# mcp801_test.net
KiCad netlist of a schematic drawn in EAGLE
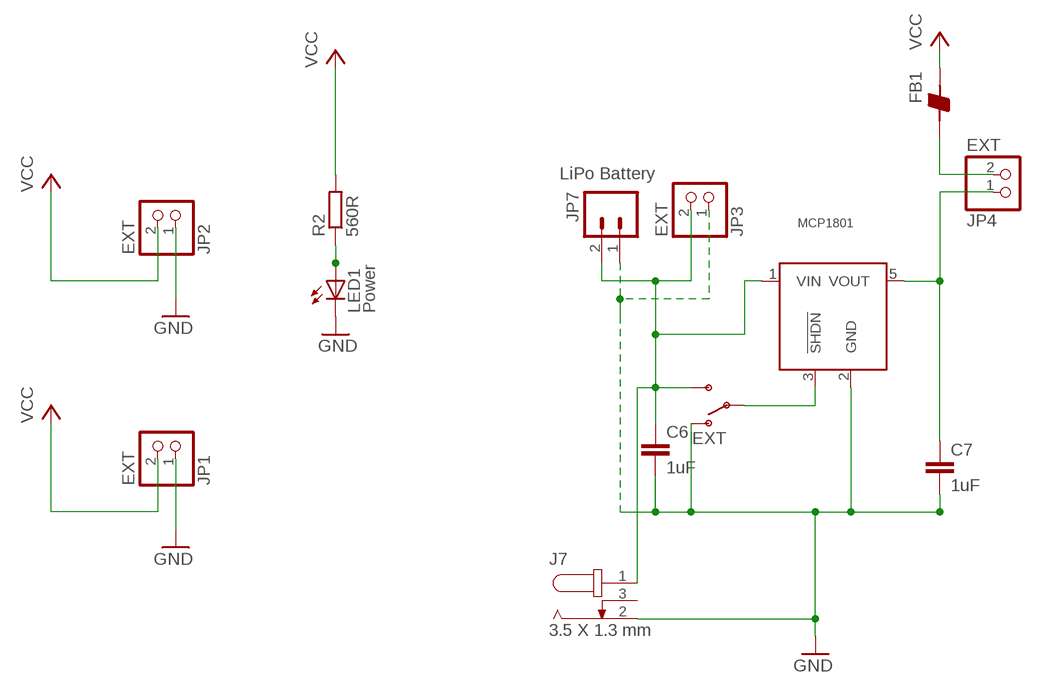
[diagram p0: schematic, sheet 1]

(export (version "E")
  (design (tool "Eeschema 10.0.6"))
  (components
    (comp (ref "C6")
      (value "1uF")
      (footprint "eagle-import:C0805")
      (libsource (lib "eagle-import") (part "C-EUC0805"))
    )
    (comp (ref "C7")
      (value "1uF")
      (footprint "eagle-import:C0805")
      (libsource (lib "eagle-import") (part "C-EUC0805"))
    )
    (comp (ref "FB1")
      (value "BEAD-0805")
      (footprint "eagle-import:0805")
      (libsource (lib "eagle-import") (part "BEAD-0805"))
    )
    (comp (ref "J7")
      (value "3.5 X 1.3 mm")
      (footprint "eagle-import:3.5X1.3MM_DC_JACK")
      (libsource (lib "eagle-import") (part "DC_JACK_3.5X1.3MM"))
    )
    (comp (ref "JP1")
      (value "EXT")
      (footprint "eagle-import:1X02")
      (libsource (lib "eagle-import") (part "PINHD-1X2"))
    )
    (comp (ref "JP2")
      (value "EXT")
      (footprint "eagle-import:1X02")
      (libsource (lib "eagle-import") (part "PINHD-1X2"))
    )
    (comp (ref "JP3")
      (value "EXT")
      (footprint "eagle-import:1X02")
      (libsource (lib "eagle-import") (part "PINHD-1X2"))
    )
    (comp (ref "JP4")
      (value "EXT")
      (footprint "eagle-import:1X02")
      (libsource (lib "eagle-import") (part "PINHD-1X2"))
    )
    (comp (ref "JP7")
      (value "LiPo Battery")
      (footprint "eagle-import:JST-2-PTH")
      (libsource (lib "eagle-import") (part "M02JST-PTH-2"))
    )
    (comp (ref "LED1")
      (value "Power")
      (footprint "eagle-import:CHIPLED_1206")
      (libsource (lib "eagle-import") (part "LEDCHIPLED_1206"))
    )
    (comp (ref "MCP1801")
      (value "MCP180XSOT-23-5")
      (footprint "eagle-import:SOT-23-5")
      (libsource (lib "eagle-import") (part "MCP180XSOT-23-5"))
    )
    (comp (ref "ON")
      (value "EXT")
      (footprint "eagle-import:SWITCH-SPDT")
      (libsource (lib "eagle-import") (part "SWITCH-SPSTPTH"))
    )
    (comp (ref "R2")
      (value "560R")
      (footprint "eagle-import:R0805")
      (libsource (lib "eagle-import") (part "R-EU_R0805"))
    )
  )
  (nets
    (net (code "1") (name "GND") (class "Default")
      (node (ref "C6") (pin "2") (pinfunction "2_2") (pintype "passive"))
      (node (ref "C7") (pin "2") (pinfunction "2_2") (pintype "passive"))
      (node (ref "J7") (pin "2") (pinfunction "2_2") (pintype "passive"))
      (node (ref "JP1") (pin "1") (pinfunction "1_1") (pintype "passive"))
      (node (ref "JP2") (pin "1") (pinfunction "1_1") (pintype "passive"))
      (node (ref "JP3") (pin "1") (pinfunction "1_1") (pintype "passive"))
      (node (ref "JP7") (pin "1") (pinfunction "1_1") (pintype "passive"))
      (node (ref "LED1") (pin "C") (pinfunction "C_C") (pintype "passive"))
      (node (ref "MCP1801") (pin "2") (pinfunction "GND_2") (pintype "power_in"))
      (node (ref "ON") (pin "1") (pinfunction "O_1") (pintype "passive"))
    )
    (net (code "2") (name "Net-(FB1-P$1)") (class "Default")
      (node (ref "FB1") (pin "1") (pinfunction "P$1_1") (pintype "passive"))
      (node (ref "JP4") (pin "2") (pinfunction "2_2") (pintype "passive"))
    )
    (net (code "3") (name "Net-(LED1-PadA)") (class "Default")
      (node (ref "LED1") (pin "A") (pinfunction "A_A") (pintype "passive"))
      (node (ref "R2") (pin "1") (pinfunction "1_1") (pintype "passive"))
    )
    (net (code "4") (name "Net-(MCP1801-VIN)") (class "Default")
      (node (ref "C6") (pin "1") (pinfunction "1_1") (pintype "passive"))
      (node (ref "J7") (pin "1") (pinfunction "1_1") (pintype "passive"))
      (node (ref "JP3") (pin "2") (pinfunction "2_2") (pintype "passive"))
      (node (ref "JP7") (pin "2") (pinfunction "2_2") (pintype "passive"))
      (node (ref "MCP1801") (pin "1") (pinfunction "VIN_1") (pintype "power_in"))
      (node (ref "ON") (pin "3") (pinfunction "S_3") (pintype "passive"))
    )
    (net (code "5") (name "Net-(MCP1801-VOUT)") (class "Default")
      (node (ref "C7") (pin "1") (pinfunction "1_1") (pintype "passive"))
      (node (ref "JP4") (pin "1") (pinfunction "1_1") (pintype "passive"))
      (node (ref "MCP1801") (pin "5") (pinfunction "VOUT_5") (pintype "power_in"))
    )
    (net (code "6") (name "Net-(MCP1801-~{SHDN})") (class "Default")
      (node (ref "MCP1801") (pin "3") (pinfunction "~{SHDN}_3") (pintype "input"))
      (node (ref "ON") (pin "2") (pinfunction "P_2") (pintype "passive"))
    )
    (net (code "7") (name "VCC") (class "Default")
      (node (ref "FB1") (pin "2") (pinfunction "P$2_2") (pintype "passive"))
      (node (ref "JP1") (pin "2") (pinfunction "2_2") (pintype "passive"))
      (node (ref "JP2") (pin "2") (pinfunction "2_2") (pintype "passive"))
      (node (ref "R2") (pin "2") (pinfunction "2_2") (pintype "passive"))
    )
    (net (code "8") (name "unconnected-(J7-Pad3)") (class "Default")
      (node (ref "J7") (pin "3") (pinfunction "3_3") (pintype "passive"))
    )
  )
)
